# spark_pcb_2t5_schematic.net
KiCad netlist of a schematic drawn in EAGLE
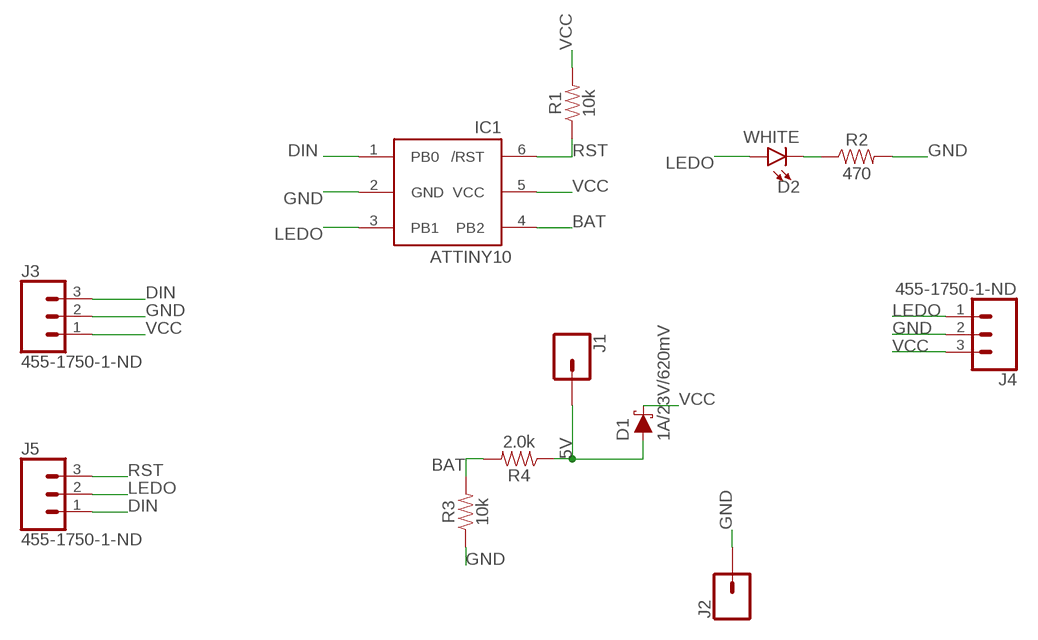
[diagram p0: schematic, sheet 1]

(export (version "E")
  (design (tool "Eeschema 10.0.6"))
  (components
    (comp (ref "D1")
      (value "1A/23V/620mV")
      (footprint "eagle-import:SOD-323")
      (libsource (lib "eagle-import") (part "DIODE-SCHOTTKY-BAT20J"))
    )
    (comp (ref "D2")
      (value "WHITE")
      (footprint "eagle-import:LED-0603")
      (libsource (lib "eagle-import") (part "LED-WHITE0603"))
    )
    (comp (ref "IC1")
      (value "ATTINY10")
      (footprint "eagle-import:SOT23-6")
      (libsource (lib "eagle-import") (part "ATTINY10"))
    )
    (comp (ref "J1")
      (value "CONN_01")
      (footprint "eagle-import:1X01")
      (libsource (lib "eagle-import") (part "CONN_01"))
    )
    (comp (ref "J2")
      (value "CONN_01")
      (footprint "eagle-import:1X01")
      (libsource (lib "eagle-import") (part "CONN_01"))
    )
    (comp (ref "J3")
      (value "455-1750-1-ND")
      (footprint "eagle-import:1X03")
      (libsource (lib "eagle-import") (part "CONN_03"))
    )
    (comp (ref "J4")
      (value "455-1750-1-ND")
      (footprint "eagle-import:1X03")
      (libsource (lib "eagle-import") (part "CONN_03"))
    )
    (comp (ref "J5")
      (value "455-1750-1-ND")
      (footprint "eagle-import:1X03")
      (libsource (lib "eagle-import") (part "CONN_03"))
    )
    (comp (ref "R1")
      (value "10k")
      (footprint "eagle-import:0603")
      (libsource (lib "eagle-import") (part "10KOHM-0603-1/10W-1%"))
    )
    (comp (ref "R2")
      (value "470")
      (footprint "eagle-import:0603")
      (libsource (lib "eagle-import") (part "470OHM-0603-1/10W-1%"))
    )
    (comp (ref "R3")
      (value "10k")
      (footprint "eagle-import:0603")
      (libsource (lib "eagle-import") (part "10KOHM-0603-1/10W-1%"))
    )
    (comp (ref "R4")
      (value "2.0k")
      (footprint "eagle-import:0603")
      (libsource (lib "eagle-import") (part "2.0KOHM-0603-1/10W-5%"))
    )
  )
  (nets
    (net (code "1") (name "/5V") (class "Default")
      (node (ref "D1") (pin "A") (pinfunction "A_A") (pintype "passive"))
      (node (ref "J1") (pin "1") (pinfunction "1_1") (pintype "passive"))
      (node (ref "R4") (pin "1") (pinfunction "1_1") (pintype "passive"))
    )
    (net (code "2") (name "/BAT") (class "Default")
      (node (ref "IC1") (pin "4") (pinfunction "PB2_4") (pintype "bidirectional"))
      (node (ref "R3") (pin "2") (pinfunction "2_2") (pintype "passive"))
      (node (ref "R4") (pin "2") (pinfunction "2_2") (pintype "passive"))
    )
    (net (code "3") (name "/DIN") (class "Default")
      (node (ref "IC1") (pin "1") (pinfunction "PB0_1") (pintype "bidirectional"))
      (node (ref "J3") (pin "3") (pinfunction "3_3") (pintype "passive"))
      (node (ref "J5") (pin "1") (pinfunction "1_1") (pintype "passive"))
    )
    (net (code "4") (name "/GND") (class "Default")
      (node (ref "IC1") (pin "2") (pinfunction "GND_2") (pintype "power_in"))
      (node (ref "J2") (pin "1") (pinfunction "1_1") (pintype "passive"))
      (node (ref "J3") (pin "2") (pinfunction "2_2") (pintype "passive"))
      (node (ref "J4") (pin "2") (pinfunction "2_2") (pintype "passive"))
      (node (ref "R2") (pin "2") (pinfunction "2_2") (pintype "passive"))
      (node (ref "R3") (pin "1") (pinfunction "1_1") (pintype "passive"))
    )
    (net (code "5") (name "/LEDO") (class "Default")
      (node (ref "D2") (pin "A") (pinfunction "A_A") (pintype "passive"))
      (node (ref "IC1") (pin "3") (pinfunction "PB1_3") (pintype "bidirectional"))
      (node (ref "J4") (pin "1") (pinfunction "1_1") (pintype "passive"))
      (node (ref "J5") (pin "2") (pinfunction "2_2") (pintype "passive"))
    )
    (net (code "6") (name "/RST") (class "Default")
      (node (ref "IC1") (pin "6") (pinfunction "/RST_6") (pintype "bidirectional"))
      (node (ref "J5") (pin "3") (pinfunction "3_3") (pintype "passive"))
      (node (ref "R1") (pin "1") (pinfunction "1_1") (pintype "passive"))
    )
    (net (code "7") (name "/VCC") (class "Default")
      (node (ref "D1") (pin "C") (pinfunction "C_C") (pintype "passive"))
      (node (ref "IC1") (pin "5") (pinfunction "VCC_5") (pintype "power_in"))
      (node (ref "J3") (pin "1") (pinfunction "1_1") (pintype "passive"))
      (node (ref "J4") (pin "3") (pinfunction "3_3") (pintype "passive"))
      (node (ref "R1") (pin "2") (pinfunction "2_2") (pintype "passive"))
    )
    (net (code "8") (name "Net-(D2-PadC)") (class "Default")
      (node (ref "D2") (pin "C") (pinfunction "C_C") (pintype "passive"))
      (node (ref "R2") (pin "1") (pinfunction "1_1") (pintype "passive"))
    )
  )
)
